# Sheet1.net
KiCad netlist of a schematic drawn in Altium Designer
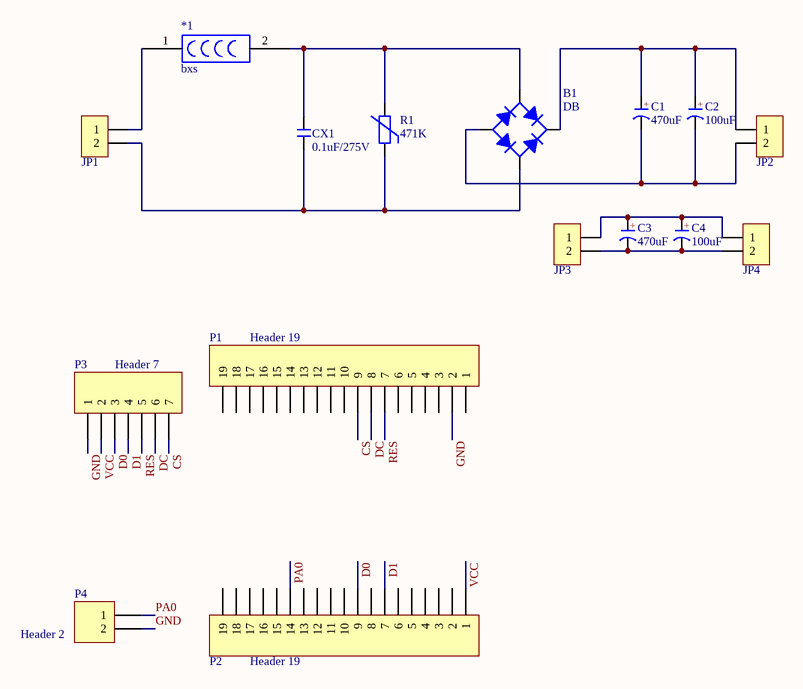
[diagram p0: Sheet1.SchDoc]

(export (version "E")
  (design (tool "Eeschema 10.0.6"))
  (components
    (comp (ref "*1") (value "bxs") (footprint "bxs") (libsource (lib "Schlib1") (part "bxs")))
    (comp (ref "B1")
      (value "DB")
      (footprint "GBU")
      (description "整流桥")
      (libsource (lib "02 - 二极管(LED)-三极管-整流桥") (part "DB"))
    )
    (comp (ref "C1")
      (value "470uF")
      (footprint "CAP 3.5*8*11.5")
      (description "直插电解电容")
      (libsource (lib "01 - 电容-电阻-电感") (part "CE"))
    )
    (comp (ref "C2")
      (value "100uF")
      (footprint "CAP 3.5*8*11.5")
      (description "直插电解电容")
      (libsource (lib "01 - 电容-电阻-电感") (part "CE"))
    )
    (comp (ref "C3")
      (value "470uF")
      (footprint "CAP 3.5*8*11.5")
      (description "直插电解电容")
      (libsource (lib "01 - 电容-电阻-电感") (part "CE"))
    )
    (comp (ref "C4")
      (value "100uF")
      (footprint "CAP 3.5*8*11.5")
      (description "直插电解电容")
      (libsource (lib "01 - 电容-电阻-电感") (part "CE"))
    )
    (comp (ref "CX1")
      (value "0.1uF/275V")
      (footprint "CX 10*13*11")
      (description "安规X电容")
      (libsource (lib "01 - 电容-电阻-电感") (part "CX"))
    )
    (comp (ref "JP1")
      (value "HDR-1X2")
      (footprint "KF2EDGK5.0-LI-2P")
      (description "2P接插件")
      (libsource (lib "21 - 接插件-脚距5.0mm") (part "Header 2"))
    )
    (comp (ref "JP2")
      (value "HDR-1X2")
      (footprint "KF2EDGK5.0-LI-2P")
      (description "2P接插件")
      (libsource (lib "01 - 电容-电阻-电感") (part "Header 2"))
    )
    (comp (ref "JP3")
      (value "HDR-1X2")
      (footprint "KF2EDGK5.0-LI-2P")
      (description "2P接插件")
      (libsource (lib "") (part "Header 2_1"))
    )
    (comp (ref "JP4")
      (value "HDR-1X2")
      (footprint "KF2EDGK5.0-LI-2P")
      (description "2P接插件")
      (libsource (lib "01 - 电容-电阻-电感") (part "Header 2"))
    )
    (comp (ref "P1")
      (value "Header 19")
      (footprint "HDR1X19")
      (description "Header, 19-Pin")
      (fields (field (name "PUBLISHER") "Altium Limited"))
      (libsource (lib "") (part "Header 19_1"))
    )
    (comp (ref "P2")
      (value "Header 19")
      (footprint "HDR1X19")
      (description "Header, 19-Pin")
      (fields (field (name "PUBLISHER") "Altium Limited"))
      (libsource (lib "Miscellaneous Connectors") (part "Header 19"))
    )
    (comp (ref "P3")
      (value "Header 7")
      (footprint "HDR1X7")
      (description "Header, 7-Pin")
      (fields (field (name "PUBLISHER") "Altium Limited"))
      (libsource (lib "Miscellaneous Connectors") (part "Header 7"))
    )
    (comp (ref "P4")
      (value "Header 2")
      (footprint "HDR1X2")
      (description "Header, 2-Pin")
      (fields (field (name "PUBLISHER") "Altium Limited"))
      (libsource (lib "Miscellaneous Connectors") (part "Header 2"))
    )
    (comp (ref "R1")
      (value "471K")
      (footprint "VDR 9D-4.5")
      (description "压敏电阻")
      (libsource (lib "01 - 电容-电阻-电感") (part "R_VSR"))
    )
  )
  (nets
    (net (code "1") (name "/CS") (class "Default")
      (node (ref "P1") (pin "9") (pinfunction "9_9") (pintype "passive"))
      (node (ref "P3") (pin "7") (pinfunction "7_7") (pintype "passive"))
    )
    (net (code "2") (name "/D0") (class "Default")
      (node (ref "P2") (pin "9") (pinfunction "9_9") (pintype "passive"))
      (node (ref "P3") (pin "3") (pinfunction "3_3") (pintype "passive"))
    )
    (net (code "3") (name "/D1") (class "Default")
      (node (ref "P2") (pin "7") (pinfunction "7_7") (pintype "passive"))
      (node (ref "P3") (pin "4") (pinfunction "4_4") (pintype "passive"))
    )
    (net (code "4") (name "/DC") (class "Default")
      (node (ref "P1") (pin "8") (pinfunction "8_8") (pintype "passive"))
      (node (ref "P3") (pin "6") (pinfunction "6_6") (pintype "passive"))
    )
    (net (code "5") (name "/GND") (class "Default")
      (node (ref "P1") (pin "2") (pinfunction "2_2") (pintype "passive"))
      (node (ref "P3") (pin "1") (pinfunction "1_1") (pintype "passive"))
      (node (ref "P4") (pin "2") (pinfunction "2_2") (pintype "passive"))
    )
    (net (code "6") (name "/PA0") (class "Default")
      (node (ref "P2") (pin "14") (pinfunction "14_14") (pintype "passive"))
      (node (ref "P4") (pin "1") (pinfunction "1_1") (pintype "passive"))
    )
    (net (code "7") (name "/RES") (class "Default")
      (node (ref "P1") (pin "7") (pinfunction "7_7") (pintype "passive"))
      (node (ref "P3") (pin "5") (pinfunction "5_5") (pintype "passive"))
    )
    (net (code "8") (name "/VCC") (class "Default")
      (node (ref "P2") (pin "1") (pinfunction "1_1") (pintype "passive"))
      (node (ref "P3") (pin "2") (pinfunction "2_2") (pintype "passive"))
    )
    (net (code "9") (name "Net-(*1-Pad1)") (class "Default")
      (node (ref "*1") (pin "1") (pinfunction "1_1") (pintype "passive"))
      (node (ref "JP1") (pin "1") (pinfunction "1_1") (pintype "passive"))
    )
    (net (code "10") (name "Net-(*1-Pad2)") (class "Default")
      (node (ref "*1") (pin "2") (pinfunction "2_2") (pintype "passive"))
      (node (ref "B1") (pin "AC1") (pinfunction "AC1_AC1") (pintype "passive"))
      (node (ref "CX1") (pin "2") (pinfunction "2_2") (pintype "passive"))
      (node (ref "R1") (pin "2") (pinfunction "2_2") (pintype "passive"))
    )
    (net (code "11") (name "Net-(B1-PadAC2)") (class "Default")
      (node (ref "B1") (pin "AC2") (pinfunction "AC2_AC2") (pintype "passive"))
      (node (ref "CX1") (pin "1") (pinfunction "1_1") (pintype "passive"))
      (node (ref "JP1") (pin "2") (pinfunction "2_2") (pintype "passive"))
      (node (ref "R1") (pin "1") (pinfunction "1_1") (pintype "passive"))
    )
    (net (code "12") (name "Net-(C1-A)") (class "Default")
      (node (ref "B1") (pin "DC+") (pinfunction "DC+_DC+") (pintype "passive"))
      (node (ref "C1") (pin "1") (pinfunction "A_1") (pintype "passive"))
      (node (ref "C2") (pin "1") (pinfunction "A_1") (pintype "passive"))
      (node (ref "JP2") (pin "1") (pinfunction "1_1") (pintype "passive"))
    )
    (net (code "13") (name "Net-(C1-K)") (class "Default")
      (node (ref "B1") (pin "DC-") (pinfunction "DC-_DC-") (pintype "passive"))
      (node (ref "C1") (pin "2") (pinfunction "K_2") (pintype "passive"))
      (node (ref "C2") (pin "2") (pinfunction "K_2") (pintype "passive"))
      (node (ref "JP2") (pin "2") (pinfunction "2_2") (pintype "passive"))
    )
    (net (code "14") (name "Net-(C3-A)") (class "Default")
      (node (ref "C3") (pin "1") (pinfunction "A_1") (pintype "passive"))
      (node (ref "C4") (pin "1") (pinfunction "A_1") (pintype "passive"))
      (node (ref "JP3") (pin "1") (pinfunction "1_1") (pintype "passive"))
      (node (ref "JP4") (pin "1") (pinfunction "1_1") (pintype "passive"))
    )
    (net (code "15") (name "Net-(C3-K)") (class "Default")
      (node (ref "C3") (pin "2") (pinfunction "K_2") (pintype "passive"))
      (node (ref "C4") (pin "2") (pinfunction "K_2") (pintype "passive"))
      (node (ref "JP3") (pin "2") (pinfunction "2_2") (pintype "passive"))
      (node (ref "JP4") (pin "2") (pinfunction "2_2") (pintype "passive"))
    )
    (net (code "16") (name "unconnected-(P1-Pad1)") (class "Default")
      (node (ref "P1") (pin "1") (pinfunction "1_1") (pintype "passive"))
    )
    (net (code "17") (name "unconnected-(P1-Pad3)") (class "Default")
      (node (ref "P1") (pin "3") (pinfunction "3_3") (pintype "passive"))
    )
    (net (code "18") (name "unconnected-(P1-Pad4)") (class "Default")
      (node (ref "P1") (pin "4") (pinfunction "4_4") (pintype "passive"))
    )
    (net (code "19") (name "unconnected-(P1-Pad5)") (class "Default")
      (node (ref "P1") (pin "5") (pinfunction "5_5") (pintype "passive"))
    )
    (net (code "20") (name "unconnected-(P1-Pad6)") (class "Default")
      (node (ref "P1") (pin "6") (pinfunction "6_6") (pintype "passive"))
    )
    (net (code "21") (name "unconnected-(P1-Pad10)") (class "Default")
      (node (ref "P1") (pin "10") (pinfunction "10_10") (pintype "passive"))
    )
    (net (code "22") (name "unconnected-(P1-Pad11)") (class "Default")
      (node (ref "P1") (pin "11") (pinfunction "11_11") (pintype "passive"))
    )
    (net (code "23") (name "unconnected-(P1-Pad12)") (class "Default")
      (node (ref "P1") (pin "12") (pinfunction "12_12") (pintype "passive"))
    )
    (net (code "24") (name "unconnected-(P1-Pad13)") (class "Default")
      (node (ref "P1") (pin "13") (pinfunction "13_13") (pintype "passive"))
    )
    (net (code "25") (name "unconnected-(P1-Pad14)") (class "Default")
      (node (ref "P1") (pin "14") (pinfunction "14_14") (pintype "passive"))
    )
    (net (code "26") (name "unconnected-(P1-Pad15)") (class "Default")
      (node (ref "P1") (pin "15") (pinfunction "15_15") (pintype "passive"))
    )
    (net (code "27") (name "unconnected-(P1-Pad16)") (class "Default")
      (node (ref "P1") (pin "16") (pinfunction "16_16") (pintype "passive"))
    )
    (net (code "28") (name "unconnected-(P1-Pad17)") (class "Default")
      (node (ref "P1") (pin "17") (pinfunction "17_17") (pintype "passive"))
    )
    (net (code "29") (name "unconnected-(P1-Pad18)") (class "Default")
      (node (ref "P1") (pin "18") (pinfunction "18_18") (pintype "passive"))
    )
    (net (code "30") (name "unconnected-(P1-Pad19)") (class "Default")
      (node (ref "P1") (pin "19") (pinfunction "19_19") (pintype "passive"))
    )
    (net (code "31") (name "unconnected-(P2-Pad2)") (class "Default")
      (node (ref "P2") (pin "2") (pinfunction "2_2") (pintype "passive"))
    )
    (net (code "32") (name "unconnected-(P2-Pad3)") (class "Default")
      (node (ref "P2") (pin "3") (pinfunction "3_3") (pintype "passive"))
    )
    (net (code "33") (name "unconnected-(P2-Pad4)") (class "Default")
      (node (ref "P2") (pin "4") (pinfunction "4_4") (pintype "passive"))
    )
    (net (code "34") (name "unconnected-(P2-Pad5)") (class "Default")
      (node (ref "P2") (pin "5") (pinfunction "5_5") (pintype "passive"))
    )
    (net (code "35") (name "unconnected-(P2-Pad6)") (class "Default")
      (node (ref "P2") (pin "6") (pinfunction "6_6") (pintype "passive"))
    )
    (net (code "36") (name "unconnected-(P2-Pad8)") (class "Default")
      (node (ref "P2") (pin "8") (pinfunction "8_8") (pintype "passive"))
    )
    (net (code "37") (name "unconnected-(P2-Pad10)") (class "Default")
      (node (ref "P2") (pin "10") (pinfunction "10_10") (pintype "passive"))
    )
    (net (code "38") (name "unconnected-(P2-Pad11)") (class "Default")
      (node (ref "P2") (pin "11") (pinfunction "11_11") (pintype "passive"))
    )
    (net (code "39") (name "unconnected-(P2-Pad12)") (class "Default")
      (node (ref "P2") (pin "12") (pinfunction "12_12") (pintype "passive"))
    )
    (net (code "40") (name "unconnected-(P2-Pad13)") (class "Default")
      (node (ref "P2") (pin "13") (pinfunction "13_13") (pintype "passive"))
    )
    (net (code "41") (name "unconnected-(P2-Pad15)") (class "Default")
      (node (ref "P2") (pin "15") (pinfunction "15_15") (pintype "passive"))
    )
    (net (code "42") (name "unconnected-(P2-Pad16)") (class "Default")
      (node (ref "P2") (pin "16") (pinfunction "16_16") (pintype "passive"))
    )
    (net (code "43") (name "unconnected-(P2-Pad17)") (class "Default")
      (node (ref "P2") (pin "17") (pinfunction "17_17") (pintype "passive"))
    )
    (net (code "44") (name "unconnected-(P2-Pad18)") (class "Default")
      (node (ref "P2") (pin "18") (pinfunction "18_18") (pintype "passive"))
    )
    (net (code "45") (name "unconnected-(P2-Pad19)") (class "Default")
      (node (ref "P2") (pin "19") (pinfunction "19_19") (pintype "passive"))
    )
  )
)
